# solar_cell.net
KiCad netlist of a schematic drawn in Altium Designer
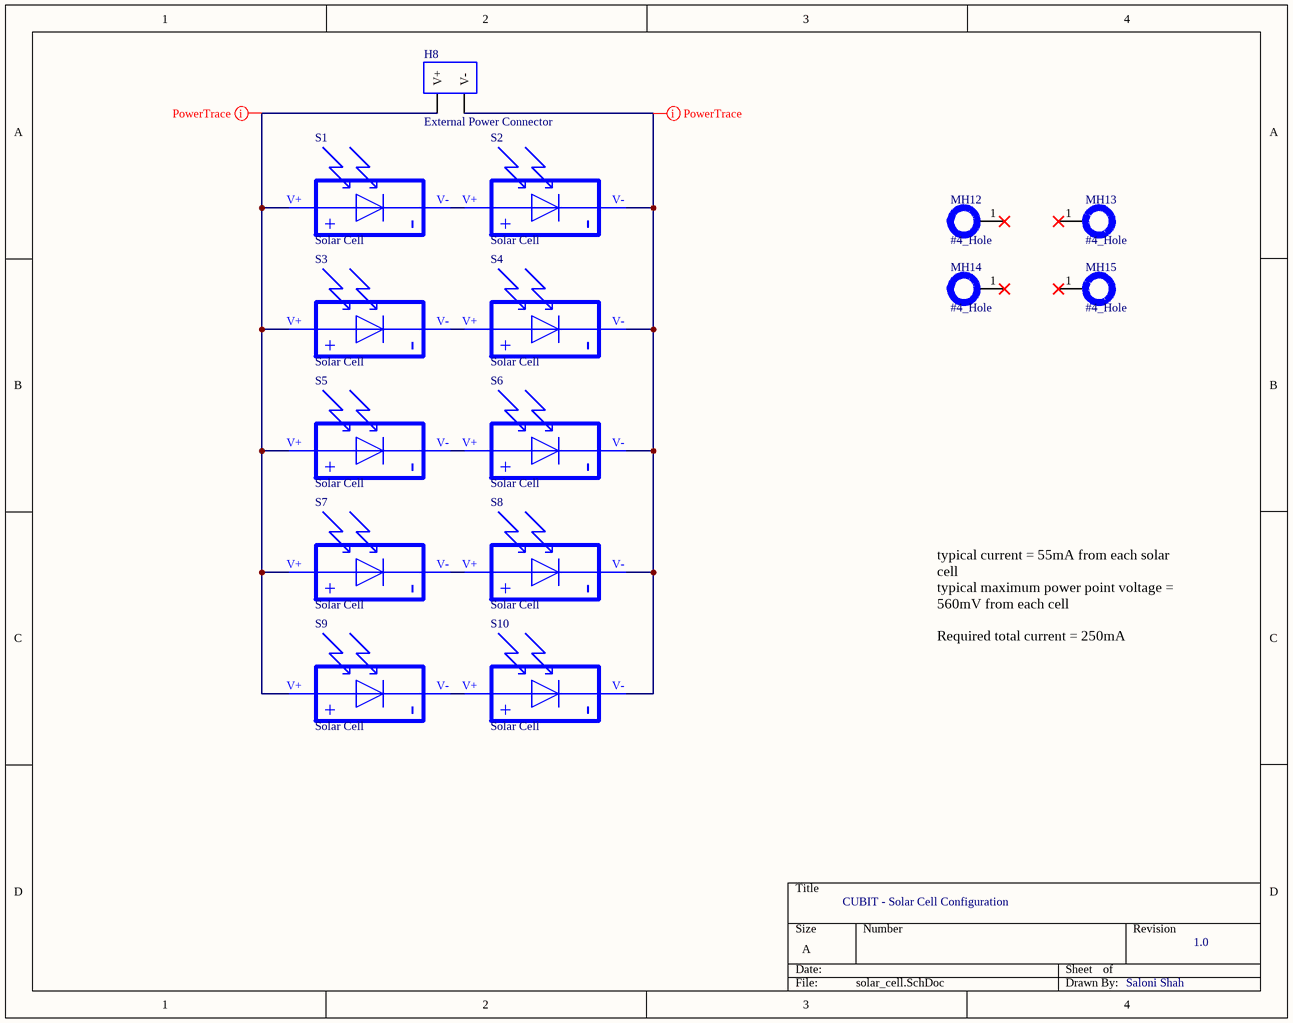
[diagram p0: solar_cell.SchDoc]

(export (version "E")
  (design (tool "Eeschema 10.0.6"))
  (components
    (comp (ref "H8")
      (value "External Power Connector")
      (footprint "LPEDT_proj_lib:2_PIN_100mil")
      (libsource (lib "LPEDT_proj_lib") (part "ext_pwr_conn"))
    )
    (comp (ref "MH12")
      (value "#4_Hole")
      (footprint "LPEDT_proj_lib:HOLE_#4")
      (libsource (lib "LPEDT_proj_lib") (part "Mechanical_Hole"))
    )
    (comp (ref "MH13")
      (value "#4_Hole")
      (footprint "LPEDT_proj_lib:HOLE_#4")
      (libsource (lib "LPEDT_proj_lib") (part "Mechanical_Hole"))
    )
    (comp (ref "MH14")
      (value "#4_Hole")
      (footprint "LPEDT_proj_lib:HOLE_#4")
      (libsource (lib "LPEDT_proj_lib") (part "Mechanical_Hole"))
    )
    (comp (ref "MH15")
      (value "#4_Hole")
      (footprint "LPEDT_proj_lib:HOLE_#4")
      (libsource (lib "LPEDT_proj_lib") (part "Mechanical_Hole"))
    )
    (comp (ref "S1")
      (value "Solar Cell")
      (footprint "KXOB25-14X1F")
      (description "MONOCRYS SOLAR CELL 30.7MW 690MV")
      (fields (field (name "MP") "KXOB25-14X1F") (field (name "MF") "ANYSOLAR Ltd"))
      (libsource (lib "LPEDT_proj_lib") (part "KXOB25-14X1F"))
    )
    (comp (ref "S2")
      (value "Solar Cell")
      (footprint "KXOB25-14X1F")
      (description "MONOCRYS SOLAR CELL 30.7MW 690MV")
      (fields (field (name "MP") "KXOB25-14X1F") (field (name "MF") "ANYSOLAR Ltd"))
      (libsource (lib "LPEDT_proj_lib") (part "KXOB25-14X1F"))
    )
    (comp (ref "S3")
      (value "Solar Cell")
      (footprint "KXOB25-14X1F")
      (description "MONOCRYS SOLAR CELL 30.7MW 690MV")
      (fields (field (name "MP") "KXOB25-14X1F") (field (name "MF") "ANYSOLAR Ltd"))
      (libsource (lib "LPEDT_proj_lib") (part "KXOB25-14X1F"))
    )
    (comp (ref "S4")
      (value "Solar Cell")
      (footprint "KXOB25-14X1F")
      (description "MONOCRYS SOLAR CELL 30.7MW 690MV")
      (fields (field (name "MP") "KXOB25-14X1F") (field (name "MF") "ANYSOLAR Ltd"))
      (libsource (lib "LPEDT_proj_lib") (part "KXOB25-14X1F"))
    )
    (comp (ref "S5")
      (value "Solar Cell")
      (footprint "KXOB25-14X1F")
      (description "MONOCRYS SOLAR CELL 30.7MW 690MV")
      (fields (field (name "MP") "KXOB25-14X1F") (field (name "MF") "ANYSOLAR Ltd"))
      (libsource (lib "LPEDT_proj_lib") (part "KXOB25-14X1F"))
    )
    (comp (ref "S6")
      (value "Solar Cell")
      (footprint "KXOB25-14X1F")
      (description "MONOCRYS SOLAR CELL 30.7MW 690MV")
      (fields (field (name "MP") "KXOB25-14X1F") (field (name "MF") "ANYSOLAR Ltd"))
      (libsource (lib "LPEDT_proj_lib") (part "KXOB25-14X1F"))
    )
    (comp (ref "S7")
      (value "Solar Cell")
      (footprint "KXOB25-14X1F")
      (description "MONOCRYS SOLAR CELL 30.7MW 690MV")
      (fields (field (name "MP") "KXOB25-14X1F") (field (name "MF") "ANYSOLAR Ltd"))
      (libsource (lib "LPEDT_proj_lib") (part "KXOB25-14X1F"))
    )
    (comp (ref "S8")
      (value "Solar Cell")
      (footprint "KXOB25-14X1F")
      (description "MONOCRYS SOLAR CELL 30.7MW 690MV")
      (fields (field (name "MP") "KXOB25-14X1F") (field (name "MF") "ANYSOLAR Ltd"))
      (libsource (lib "LPEDT_proj_lib") (part "KXOB25-14X1F"))
    )
    (comp (ref "S9")
      (value "Solar Cell")
      (footprint "KXOB25-14X1F")
      (description "MONOCRYS SOLAR CELL 30.7MW 690MV")
      (fields (field (name "MP") "KXOB25-14X1F") (field (name "MF") "ANYSOLAR Ltd"))
      (libsource (lib "LPEDT_proj_lib") (part "KXOB25-14X1F"))
    )
    (comp (ref "S10")
      (value "Solar Cell")
      (footprint "KXOB25-14X1F")
      (description "MONOCRYS SOLAR CELL 30.7MW 690MV")
      (fields (field (name "MP") "KXOB25-14X1F") (field (name "MF") "ANYSOLAR Ltd"))
      (libsource (lib "LPEDT_proj_lib") (part "KXOB25-14X1F"))
    )
  )
  (nets
    (net (code "1") (name "Net-(H8-V+)") (class "Default")
      (node (ref "H8") (pin "1") (pinfunction "V+_1") (pintype "passive"))
      (node (ref "S1") (pin "V+") (pintype "power_in"))
      (node (ref "S3") (pin "V+") (pintype "power_in"))
      (node (ref "S5") (pin "V+") (pintype "power_in"))
      (node (ref "S7") (pin "V+") (pintype "power_in"))
      (node (ref "S9") (pin "V+") (pintype "power_in"))
    )
    (net (code "2") (name "Net-(H8-V-)") (class "Default")
      (node (ref "H8") (pin "2") (pinfunction "V-_2") (pintype "passive"))
      (node (ref "S10") (pin "V-") (pintype "power_in"))
      (node (ref "S2") (pin "V-") (pintype "power_in"))
      (node (ref "S4") (pin "V-") (pintype "power_in"))
      (node (ref "S6") (pin "V-") (pintype "power_in"))
      (node (ref "S8") (pin "V-") (pintype "power_in"))
    )
    (net (code "3") (name "Net-(S1-PadV-)") (class "Default")
      (node (ref "S1") (pin "V-") (pintype "power_in"))
      (node (ref "S2") (pin "V+") (pintype "power_in"))
    )
    (net (code "4") (name "Net-(S3-PadV-)") (class "Default")
      (node (ref "S3") (pin "V-") (pintype "power_in"))
      (node (ref "S4") (pin "V+") (pintype "power_in"))
    )
    (net (code "5") (name "Net-(S5-PadV-)") (class "Default")
      (node (ref "S5") (pin "V-") (pintype "power_in"))
      (node (ref "S6") (pin "V+") (pintype "power_in"))
    )
    (net (code "6") (name "Net-(S7-PadV-)") (class "Default")
      (node (ref "S7") (pin "V-") (pintype "power_in"))
      (node (ref "S8") (pin "V+") (pintype "power_in"))
    )
    (net (code "7") (name "Net-(S10-PadV+)") (class "Default")
      (node (ref "S10") (pin "V+") (pintype "power_in"))
      (node (ref "S9") (pin "V-") (pintype "power_in"))
    )
    (net (code "8") (name "unconnected-(MH12-Pad1)") (class "Default")
      (node (ref "MH12") (pin "1") (pinfunction "1_1") (pintype "passive+no_connect"))
    )
    (net (code "9") (name "unconnected-(MH13-Pad1)") (class "Default")
      (node (ref "MH13") (pin "1") (pinfunction "1_1") (pintype "passive+no_connect"))
    )
    (net (code "10") (name "unconnected-(MH14-Pad1)") (class "Default")
      (node (ref "MH14") (pin "1") (pinfunction "1_1") (pintype "passive+no_connect"))
    )
    (net (code "11") (name "unconnected-(MH15-Pad1)") (class "Default")
      (node (ref "MH15") (pin "1") (pinfunction "1_1") (pintype "passive+no_connect"))
    )
  )
)
